# Capsense16_25092018.net
KiCad netlist of a schematic drawn in EAGLE
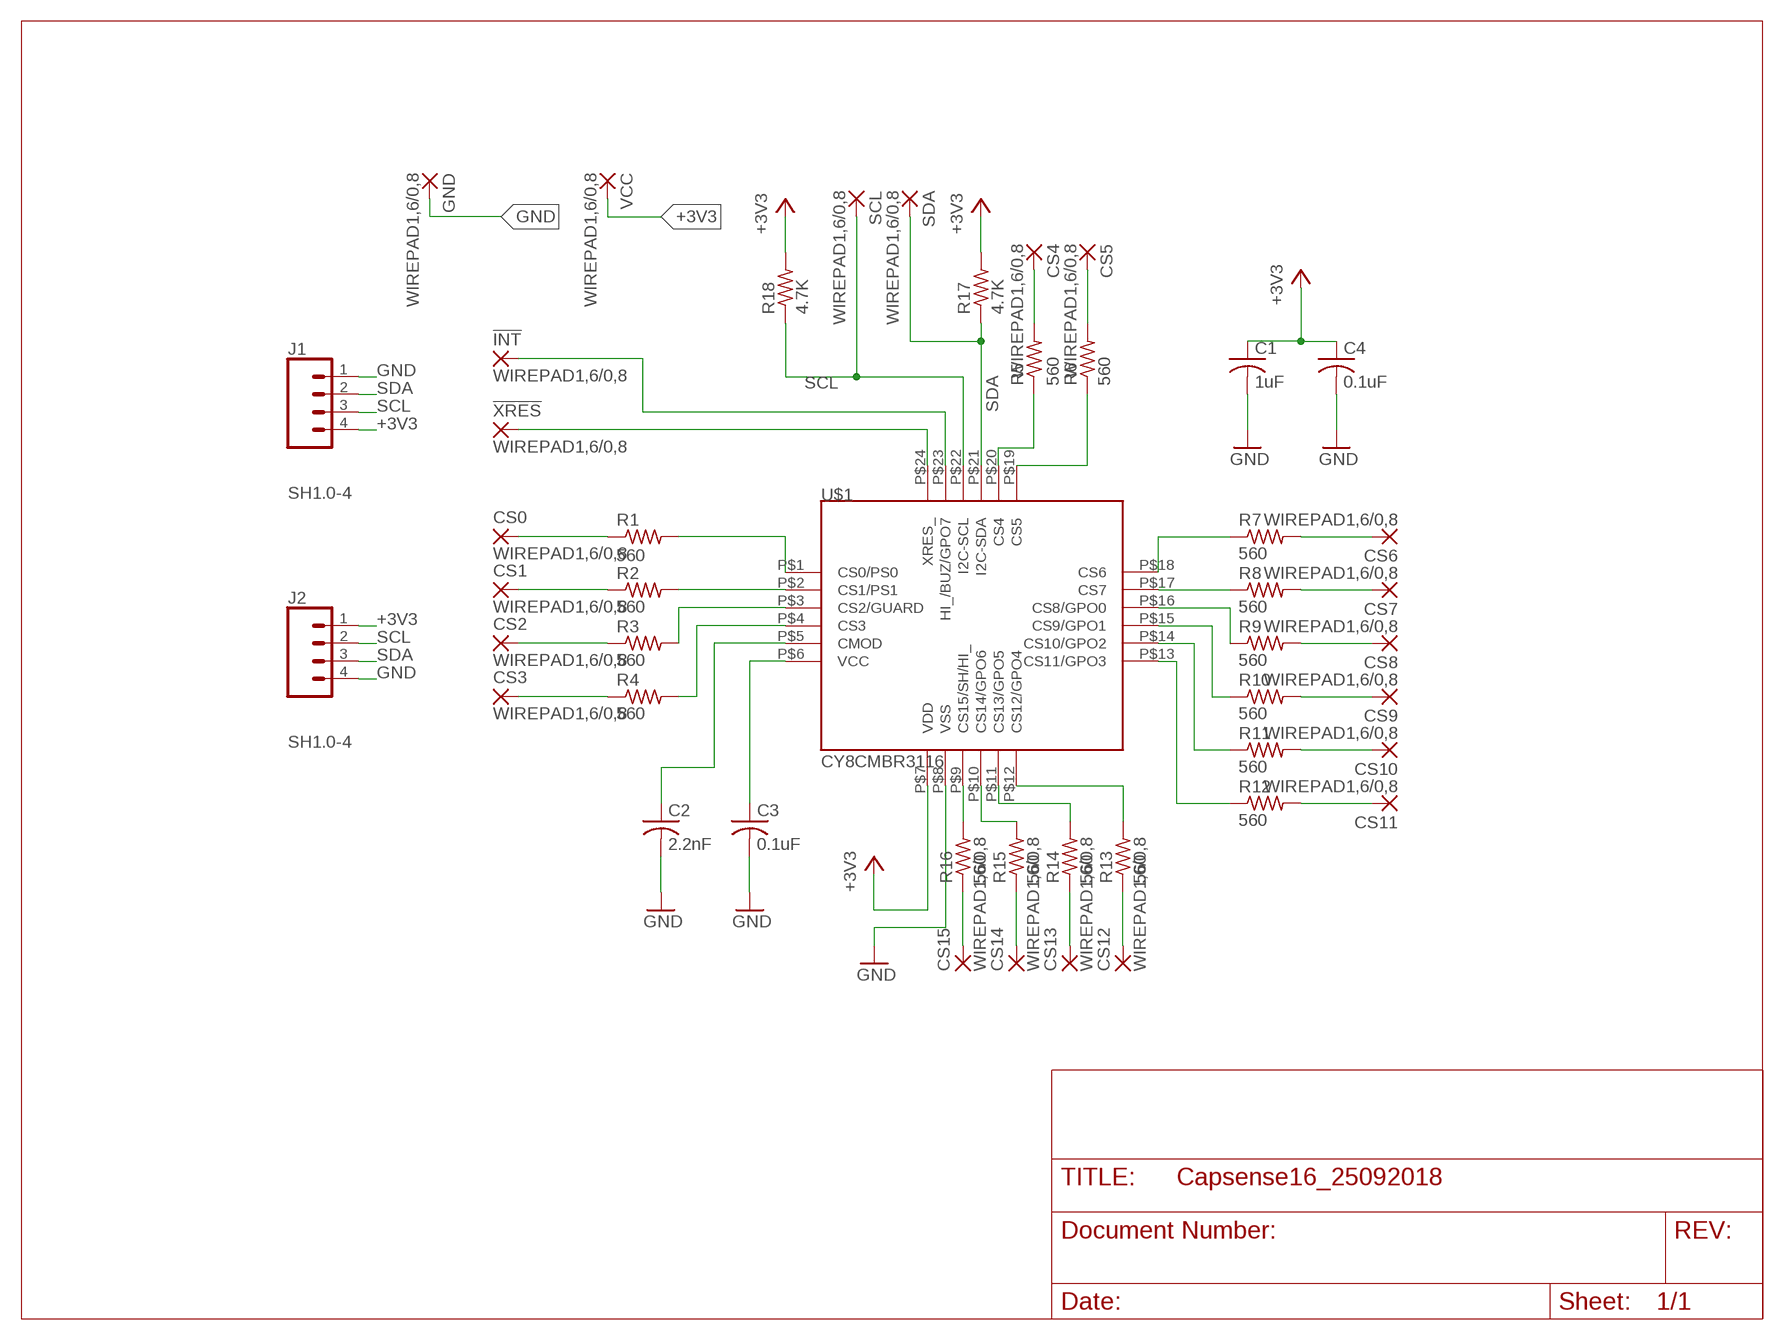
[diagram p0: schematic, sheet 1]

(export (version "E")
  (design (tool "Eeschema 10.0.6"))
  (components
    (comp (ref "!INT!")
      (value "WIREPAD1,6/0,8")
      (footprint "eagle-import:1,6_0,8")
      (libsource (lib "eagle-import") (part "WIREPAD1,6/0,8"))
    )
    (comp (ref "!XRES!")
      (value "WIREPAD1,6/0,8")
      (footprint "eagle-import:1,6_0,8")
      (libsource (lib "eagle-import") (part "WIREPAD1,6/0,8"))
    )
    (comp (ref "C1")
      (value "1uF")
      (footprint "eagle-import:C0603")
      (libsource (lib "eagle-import") (part "C-USC0603"))
    )
    (comp (ref "C2")
      (value "2.2nF")
      (footprint "eagle-import:C0603")
      (libsource (lib "eagle-import") (part "C-USC0603"))
    )
    (comp (ref "C3")
      (value "0.1uF")
      (footprint "eagle-import:C0603")
      (libsource (lib "eagle-import") (part "C-USC0603"))
    )
    (comp (ref "C4")
      (value "0.1uF")
      (footprint "eagle-import:C0603")
      (libsource (lib "eagle-import") (part "C-USC0603"))
    )
    (comp (ref "CS0")
      (value "WIREPAD1,6/0,8")
      (footprint "eagle-import:1,6_0,8")
      (libsource (lib "eagle-import") (part "WIREPAD1,6/0,8"))
    )
    (comp (ref "CS1")
      (value "WIREPAD1,6/0,8")
      (footprint "eagle-import:1,6_0,8")
      (libsource (lib "eagle-import") (part "WIREPAD1,6/0,8"))
    )
    (comp (ref "CS2")
      (value "WIREPAD1,6/0,8")
      (footprint "eagle-import:1,6_0,8")
      (libsource (lib "eagle-import") (part "WIREPAD1,6/0,8"))
    )
    (comp (ref "CS3")
      (value "WIREPAD1,6/0,8")
      (footprint "eagle-import:1,6_0,8")
      (libsource (lib "eagle-import") (part "WIREPAD1,6/0,8"))
    )
    (comp (ref "CS4")
      (value "WIREPAD1,6/0,8")
      (footprint "eagle-import:1,6_0,8")
      (libsource (lib "eagle-import") (part "WIREPAD1,6/0,8"))
    )
    (comp (ref "CS5")
      (value "WIREPAD1,6/0,8")
      (footprint "eagle-import:1,6_0,8")
      (libsource (lib "eagle-import") (part "WIREPAD1,6/0,8"))
    )
    (comp (ref "CS6")
      (value "WIREPAD1,6/0,8")
      (footprint "eagle-import:1,6_0,8")
      (libsource (lib "eagle-import") (part "WIREPAD1,6/0,8"))
    )
    (comp (ref "CS7")
      (value "WIREPAD1,6/0,8")
      (footprint "eagle-import:1,6_0,8")
      (libsource (lib "eagle-import") (part "WIREPAD1,6/0,8"))
    )
    (comp (ref "CS8")
      (value "WIREPAD1,6/0,8")
      (footprint "eagle-import:1,6_0,8")
      (libsource (lib "eagle-import") (part "WIREPAD1,6/0,8"))
    )
    (comp (ref "CS9")
      (value "WIREPAD1,6/0,8")
      (footprint "eagle-import:1,6_0,8")
      (libsource (lib "eagle-import") (part "WIREPAD1,6/0,8"))
    )
    (comp (ref "CS10")
      (value "WIREPAD1,6/0,8")
      (footprint "eagle-import:1,6_0,8")
      (libsource (lib "eagle-import") (part "WIREPAD1,6/0,8"))
    )
    (comp (ref "CS11")
      (value "WIREPAD1,6/0,8")
      (footprint "eagle-import:1,6_0,8")
      (libsource (lib "eagle-import") (part "WIREPAD1,6/0,8"))
    )
    (comp (ref "CS12")
      (value "WIREPAD1,6/0,8")
      (footprint "eagle-import:1,6_0,8")
      (libsource (lib "eagle-import") (part "WIREPAD1,6/0,8"))
    )
    (comp (ref "CS13")
      (value "WIREPAD1,6/0,8")
      (footprint "eagle-import:1,6_0,8")
      (libsource (lib "eagle-import") (part "WIREPAD1,6/0,8"))
    )
    (comp (ref "CS14")
      (value "WIREPAD1,6/0,8")
      (footprint "eagle-import:1,6_0,8")
      (libsource (lib "eagle-import") (part "WIREPAD1,6/0,8"))
    )
    (comp (ref "CS15")
      (value "WIREPAD1,6/0,8")
      (footprint "eagle-import:1,6_0,8")
      (libsource (lib "eagle-import") (part "WIREPAD1,6/0,8"))
    )
    (comp (ref "GND")
      (value "WIREPAD1,6/0,8")
      (footprint "eagle-import:1,6_0,8")
      (libsource (lib "eagle-import") (part "WIREPAD1,6/0,8"))
    )
    (comp (ref "J1")
      (value "SH1.0-4")
      (footprint "eagle-import:JST-4-SMD-HORI-1.0MM")
      (libsource (lib "eagle-import") (part "JST_4_PIN_HORIZONTAL"))
    )
    (comp (ref "J2")
      (value "SH1.0-4")
      (footprint "eagle-import:JST-4-SMD-HORI-1.0MM")
      (libsource (lib "eagle-import") (part "JST_4_PIN_HORIZONTAL"))
    )
    (comp (ref "R1")
      (value "560")
      (footprint "eagle-import:R0603")
      (libsource (lib "eagle-import") (part "R-US_R0603"))
    )
    (comp (ref "R2")
      (value "560")
      (footprint "eagle-import:R0603")
      (libsource (lib "eagle-import") (part "R-US_R0603"))
    )
    (comp (ref "R3")
      (value "560")
      (footprint "eagle-import:R0603")
      (libsource (lib "eagle-import") (part "R-US_R0603"))
    )
    (comp (ref "R4")
      (value "560")
      (footprint "eagle-import:R0603")
      (libsource (lib "eagle-import") (part "R-US_R0603"))
    )
    (comp (ref "R5")
      (value "560")
      (footprint "eagle-import:R0603")
      (libsource (lib "eagle-import") (part "R-US_R0603"))
    )
    (comp (ref "R6")
      (value "560")
      (footprint "eagle-import:R0603")
      (libsource (lib "eagle-import") (part "R-US_R0603"))
    )
    (comp (ref "R7")
      (value "560")
      (footprint "eagle-import:R0603")
      (libsource (lib "eagle-import") (part "R-US_R0603"))
    )
    (comp (ref "R8")
      (value "560")
      (footprint "eagle-import:R0603")
      (libsource (lib "eagle-import") (part "R-US_R0603"))
    )
    (comp (ref "R9")
      (value "560")
      (footprint "eagle-import:R0603")
      (libsource (lib "eagle-import") (part "R-US_R0603"))
    )
    (comp (ref "R10")
      (value "560")
      (footprint "eagle-import:R0603")
      (libsource (lib "eagle-import") (part "R-US_R0603"))
    )
    (comp (ref "R11")
      (value "560")
      (footprint "eagle-import:R0603")
      (libsource (lib "eagle-import") (part "R-US_R0603"))
    )
    (comp (ref "R12")
      (value "560")
      (footprint "eagle-import:R0603")
      (libsource (lib "eagle-import") (part "R-US_R0603"))
    )
    (comp (ref "R13")
      (value "560")
      (footprint "eagle-import:R0603")
      (libsource (lib "eagle-import") (part "R-US_R0603"))
    )
    (comp (ref "R14")
      (value "560")
      (footprint "eagle-import:R0603")
      (libsource (lib "eagle-import") (part "R-US_R0603"))
    )
    (comp (ref "R15")
      (value "560")
      (footprint "eagle-import:R0603")
      (libsource (lib "eagle-import") (part "R-US_R0603"))
    )
    (comp (ref "R16")
      (value "560")
      (footprint "eagle-import:R0603")
      (libsource (lib "eagle-import") (part "R-US_R0603"))
    )
    (comp (ref "R17")
      (value "4.7K")
      (footprint "eagle-import:R0603")
      (libsource (lib "eagle-import") (part "R-US_R0603"))
    )
    (comp (ref "R18")
      (value "4.7K")
      (footprint "eagle-import:R0603")
      (libsource (lib "eagle-import") (part "R-US_R0603"))
    )
    (comp (ref "SCL")
      (value "WIREPAD1,6/0,8")
      (footprint "eagle-import:1,6_0,8")
      (libsource (lib "eagle-import") (part "WIREPAD1,6/0,8"))
    )
    (comp (ref "SDA")
      (value "WIREPAD1,6/0,8")
      (footprint "eagle-import:1,6_0,8")
      (libsource (lib "eagle-import") (part "WIREPAD1,6/0,8"))
    )
    (comp (ref "U$1")
      (value "CY8CMBR3116")
      (footprint "eagle-import:CY8CMBR3116")
      (libsource (lib "eagle-import") (part "CY8CMBR3116"))
    )
    (comp (ref "VCC")
      (value "WIREPAD1,6/0,8")
      (footprint "eagle-import:1,6_0,8")
      (libsource (lib "eagle-import") (part "WIREPAD1,6/0,8"))
    )
  )
  (nets
    (net (code "1") (name "+3V3") (class "Default")
      (node (ref "C1") (pin "1") (pinfunction "1_1") (pintype "passive"))
      (node (ref "C4") (pin "1") (pinfunction "1_1") (pintype "passive"))
      (node (ref "J1") (pin "4") (pinfunction "4_4") (pintype "passive"))
      (node (ref "J2") (pin "1") (pinfunction "1_1") (pintype "passive"))
      (node (ref "R17") (pin "2") (pinfunction "2_2") (pintype "passive"))
      (node (ref "R18") (pin "2") (pinfunction "2_2") (pintype "passive"))
      (node (ref "U$1") (pin "P$7") (pinfunction "VDD_P$7") (pintype "bidirectional"))
      (node (ref "VCC") (pin "1") (pinfunction "P_1") (pintype "passive"))
    )
    (net (code "2") (name "/SCL") (class "Default")
      (node (ref "J1") (pin "3") (pinfunction "3_3") (pintype "passive"))
      (node (ref "J2") (pin "2") (pinfunction "2_2") (pintype "passive"))
      (node (ref "R18") (pin "1") (pinfunction "1_1") (pintype "passive"))
      (node (ref "SCL") (pin "1") (pinfunction "P_1") (pintype "passive"))
      (node (ref "U$1") (pin "P$22") (pinfunction "I2C-SCL_P$22") (pintype "bidirectional"))
    )
    (net (code "3") (name "/SDA") (class "Default")
      (node (ref "J1") (pin "2") (pinfunction "2_2") (pintype "passive"))
      (node (ref "J2") (pin "3") (pinfunction "3_3") (pintype "passive"))
      (node (ref "R17") (pin "1") (pinfunction "1_1") (pintype "passive"))
      (node (ref "SDA") (pin "1") (pinfunction "P_1") (pintype "passive"))
      (node (ref "U$1") (pin "P$21") (pinfunction "I2C-SDA_P$21") (pintype "bidirectional"))
    )
    (net (code "4") (name "GND") (class "Default")
      (node (ref "C1") (pin "2") (pinfunction "2_2") (pintype "passive"))
      (node (ref "C2") (pin "2") (pinfunction "2_2") (pintype "passive"))
      (node (ref "C3") (pin "2") (pinfunction "2_2") (pintype "passive"))
      (node (ref "C4") (pin "2") (pinfunction "2_2") (pintype "passive"))
      (node (ref "GND") (pin "1") (pinfunction "P_1") (pintype "passive"))
      (node (ref "J1") (pin "1") (pinfunction "1_1") (pintype "passive"))
      (node (ref "J2") (pin "4") (pinfunction "4_4") (pintype "passive"))
      (node (ref "U$1") (pin "P$8") (pinfunction "VSS_P$8") (pintype "bidirectional"))
    )
    (net (code "5") (name "Net-(!INT!-P)") (class "Default")
      (node (ref "!INT!") (pin "1") (pinfunction "P_1") (pintype "passive"))
      (node (ref "U$1") (pin "P$23") (pinfunction "HI_/BUZ/GPO7_P$23") (pintype "bidirectional"))
    )
    (net (code "6") (name "Net-(!XRES!-P)") (class "Default")
      (node (ref "!XRES!") (pin "1") (pinfunction "P_1") (pintype "passive"))
      (node (ref "U$1") (pin "P$24") (pinfunction "XRES__P$24") (pintype "bidirectional"))
    )
    (net (code "7") (name "Net-(CS0-P)") (class "Default")
      (node (ref "CS0") (pin "1") (pinfunction "P_1") (pintype "passive"))
      (node (ref "R1") (pin "1") (pinfunction "1_1") (pintype "passive"))
    )
    (net (code "8") (name "Net-(CS1-P)") (class "Default")
      (node (ref "CS1") (pin "1") (pinfunction "P_1") (pintype "passive"))
      (node (ref "R2") (pin "1") (pinfunction "1_1") (pintype "passive"))
    )
    (net (code "9") (name "Net-(CS2-P)") (class "Default")
      (node (ref "CS2") (pin "1") (pinfunction "P_1") (pintype "passive"))
      (node (ref "R3") (pin "1") (pinfunction "1_1") (pintype "passive"))
    )
    (net (code "10") (name "Net-(CS3-P)") (class "Default")
      (node (ref "CS3") (pin "1") (pinfunction "P_1") (pintype "passive"))
      (node (ref "R4") (pin "1") (pinfunction "1_1") (pintype "passive"))
    )
    (net (code "11") (name "Net-(CS4-P)") (class "Default")
      (node (ref "CS4") (pin "1") (pinfunction "P_1") (pintype "passive"))
      (node (ref "R5") (pin "2") (pinfunction "2_2") (pintype "passive"))
    )
    (net (code "12") (name "Net-(CS5-P)") (class "Default")
      (node (ref "CS5") (pin "1") (pinfunction "P_1") (pintype "passive"))
      (node (ref "R6") (pin "2") (pinfunction "2_2") (pintype "passive"))
    )
    (net (code "13") (name "Net-(CS6-P)") (class "Default")
      (node (ref "CS6") (pin "1") (pinfunction "P_1") (pintype "passive"))
      (node (ref "R7") (pin "2") (pinfunction "2_2") (pintype "passive"))
    )
    (net (code "14") (name "Net-(CS7-P)") (class "Default")
      (node (ref "CS7") (pin "1") (pinfunction "P_1") (pintype "passive"))
      (node (ref "R8") (pin "2") (pinfunction "2_2") (pintype "passive"))
    )
    (net (code "15") (name "Net-(CS8-P)") (class "Default")
      (node (ref "CS8") (pin "1") (pinfunction "P_1") (pintype "passive"))
      (node (ref "R9") (pin "2") (pinfunction "2_2") (pintype "passive"))
    )
    (net (code "16") (name "Net-(CS9-P)") (class "Default")
      (node (ref "CS9") (pin "1") (pinfunction "P_1") (pintype "passive"))
      (node (ref "R10") (pin "2") (pinfunction "2_2") (pintype "passive"))
    )
    (net (code "17") (name "Net-(CS10-P)") (class "Default")
      (node (ref "CS10") (pin "1") (pinfunction "P_1") (pintype "passive"))
      (node (ref "R11") (pin "2") (pinfunction "2_2") (pintype "passive"))
    )
    (net (code "18") (name "Net-(CS11-P)") (class "Default")
      (node (ref "CS11") (pin "1") (pinfunction "P_1") (pintype "passive"))
      (node (ref "R12") (pin "2") (pinfunction "2_2") (pintype "passive"))
    )
    (net (code "19") (name "Net-(CS12-P)") (class "Default")
      (node (ref "CS12") (pin "1") (pinfunction "P_1") (pintype "passive"))
      (node (ref "R13") (pin "1") (pinfunction "1_1") (pintype "passive"))
    )
    (net (code "20") (name "Net-(CS13-P)") (class "Default")
      (node (ref "CS13") (pin "1") (pinfunction "P_1") (pintype "passive"))
      (node (ref "R14") (pin "1") (pinfunction "1_1") (pintype "passive"))
    )
    (net (code "21") (name "Net-(CS14-P)") (class "Default")
      (node (ref "CS14") (pin "1") (pinfunction "P_1") (pintype "passive"))
      (node (ref "R15") (pin "1") (pinfunction "1_1") (pintype "passive"))
    )
    (net (code "22") (name "Net-(CS15-P)") (class "Default")
      (node (ref "CS15") (pin "1") (pinfunction "P_1") (pintype "passive"))
      (node (ref "R16") (pin "1") (pinfunction "1_1") (pintype "passive"))
    )
    (net (code "23") (name "Net-(U$1-CMOD)") (class "Default")
      (node (ref "C2") (pin "1") (pinfunction "1_1") (pintype "passive"))
      (node (ref "U$1") (pin "P$5") (pinfunction "CMOD_P$5") (pintype "bidirectional"))
    )
    (net (code "24") (name "Net-(U$1-CS0{slash}PS0)") (class "Default")
      (node (ref "R1") (pin "2") (pinfunction "2_2") (pintype "passive"))
      (node (ref "U$1") (pin "P$1") (pinfunction "CS0/PS0_P$1") (pintype "bidirectional"))
    )
    (net (code "25") (name "Net-(U$1-CS1{slash}PS1)") (class "Default")
      (node (ref "R2") (pin "2") (pinfunction "2_2") (pintype "passive"))
      (node (ref "U$1") (pin "P$2") (pinfunction "CS1/PS1_P$2") (pintype "bidirectional"))
    )
    (net (code "26") (name "Net-(U$1-CS2{slash}GUARD)") (class "Default")
      (node (ref "R3") (pin "2") (pinfunction "2_2") (pintype "passive"))
      (node (ref "U$1") (pin "P$3") (pinfunction "CS2/GUARD_P$3") (pintype "bidirectional"))
    )
    (net (code "27") (name "Net-(U$1-CS3)") (class "Default")
      (node (ref "R4") (pin "2") (pinfunction "2_2") (pintype "passive"))
      (node (ref "U$1") (pin "P$4") (pinfunction "CS3_P$4") (pintype "bidirectional"))
    )
    (net (code "28") (name "Net-(U$1-CS4)") (class "Default")
      (node (ref "R5") (pin "1") (pinfunction "1_1") (pintype "passive"))
      (node (ref "U$1") (pin "P$20") (pinfunction "CS4_P$20") (pintype "bidirectional"))
    )
    (net (code "29") (name "Net-(U$1-CS5)") (class "Default")
      (node (ref "R6") (pin "1") (pinfunction "1_1") (pintype "passive"))
      (node (ref "U$1") (pin "P$19") (pinfunction "CS5_P$19") (pintype "bidirectional"))
    )
    (net (code "30") (name "Net-(U$1-CS6)") (class "Default")
      (node (ref "R7") (pin "1") (pinfunction "1_1") (pintype "passive"))
      (node (ref "U$1") (pin "P$18") (pinfunction "CS6_P$18") (pintype "bidirectional"))
    )
    (net (code "31") (name "Net-(U$1-CS7)") (class "Default")
      (node (ref "R8") (pin "1") (pinfunction "1_1") (pintype "passive"))
      (node (ref "U$1") (pin "P$17") (pinfunction "CS7_P$17") (pintype "bidirectional"))
    )
    (net (code "32") (name "Net-(U$1-CS8{slash}GPO0)") (class "Default")
      (node (ref "R9") (pin "1") (pinfunction "1_1") (pintype "passive"))
      (node (ref "U$1") (pin "P$16") (pinfunction "CS8/GPO0_P$16") (pintype "bidirectional"))
    )
    (net (code "33") (name "Net-(U$1-CS9{slash}GPO1)") (class "Default")
      (node (ref "R10") (pin "1") (pinfunction "1_1") (pintype "passive"))
      (node (ref "U$1") (pin "P$15") (pinfunction "CS9/GPO1_P$15") (pintype "bidirectional"))
    )
    (net (code "34") (name "Net-(U$1-CS10{slash}GPO2)") (class "Default")
      (node (ref "R11") (pin "1") (pinfunction "1_1") (pintype "passive"))
      (node (ref "U$1") (pin "P$14") (pinfunction "CS10/GPO2_P$14") (pintype "bidirectional"))
    )
    (net (code "35") (name "Net-(U$1-CS11{slash}GPO3)") (class "Default")
      (node (ref "R12") (pin "1") (pinfunction "1_1") (pintype "passive"))
      (node (ref "U$1") (pin "P$13") (pinfunction "CS11/GPO3_P$13") (pintype "bidirectional"))
    )
    (net (code "36") (name "Net-(U$1-CS12{slash}GPO4)") (class "Default")
      (node (ref "R13") (pin "2") (pinfunction "2_2") (pintype "passive"))
      (node (ref "U$1") (pin "P$12") (pinfunction "CS12/GPO4_P$12") (pintype "bidirectional"))
    )
    (net (code "37") (name "Net-(U$1-CS13{slash}GPO5)") (class "Default")
      (node (ref "R14") (pin "2") (pinfunction "2_2") (pintype "passive"))
      (node (ref "U$1") (pin "P$11") (pinfunction "CS13/GPO5_P$11") (pintype "bidirectional"))
    )
    (net (code "38") (name "Net-(U$1-CS14{slash}GPO6)") (class "Default")
      (node (ref "R15") (pin "2") (pinfunction "2_2") (pintype "passive"))
      (node (ref "U$1") (pin "P$10") (pinfunction "CS14/GPO6_P$10") (pintype "bidirectional"))
    )
    (net (code "39") (name "Net-(U$1-CS15{slash}SH{slash}HI_)") (class "Default")
      (node (ref "R16") (pin "2") (pinfunction "2_2") (pintype "passive"))
      (node (ref "U$1") (pin "P$9") (pinfunction "CS15/SH/HI__P$9") (pintype "bidirectional"))
    )
    (net (code "40") (name "Net-(U$1-VCC)") (class "Default")
      (node (ref "C3") (pin "1") (pinfunction "1_1") (pintype "passive"))
      (node (ref "U$1") (pin "P$6") (pinfunction "VCC_P$6") (pintype "bidirectional"))
    )
  )
)
